# sensors.net
KiCad netlist of a schematic drawn in EAGLE
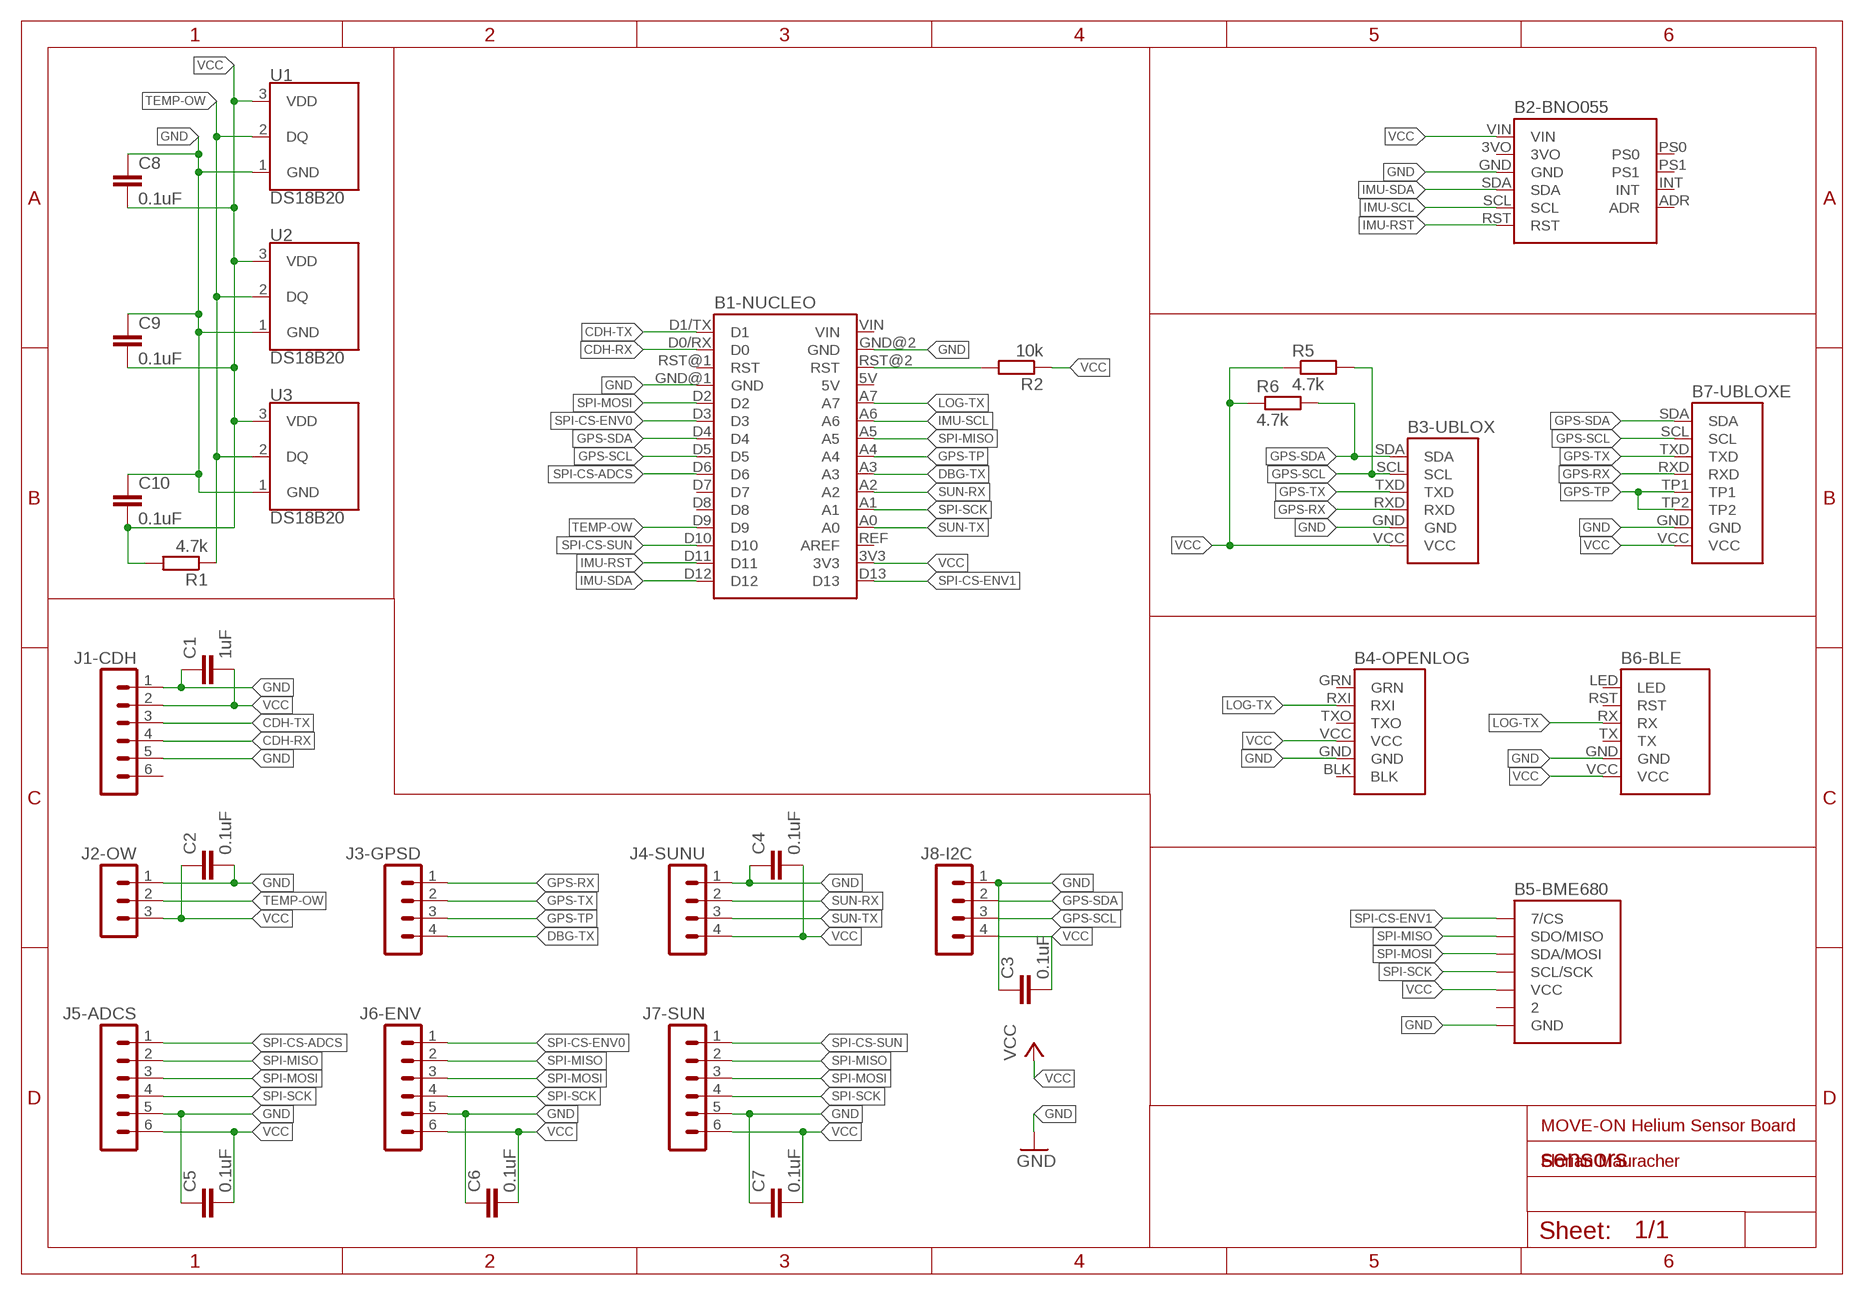
[diagram p0: schematic, sheet 1]

(export (version "E")
  (design (tool "Eeschema 10.0.6"))
  (components
    (comp (ref "B1-NUCLEO")
      (value "NUCLEO-32BO")
      (footprint "eagle-import:NUCLEO-32")
      (libsource (lib "eagle-import") (part "NUCLEO-32BO"))
    )
    (comp (ref "B2-BNO055")
      (value "BOSCH-BNO055BO")
      (footprint "eagle-import:BOSCH-BNO055")
      (libsource (lib "eagle-import") (part "BOSCH-BNO055BO"))
    )
    (comp (ref "B3-UBLOX")
      (value "UPUTRONICS-UBLOX-PICOBO")
      (footprint "eagle-import:UPUTRONICS-UBLOX-PICO")
      (libsource (lib "eagle-import") (part "UPUTRONICS-UBLOX-PICOBO"))
    )
    (comp (ref "B4-OPENLOG")
      (value "SPARKFUN-OPENLOGBO")
      (footprint "eagle-import:SPARKFUN-OPENLOG")
      (libsource (lib "eagle-import") (part "SPARKFUN-OPENLOGBO"))
    )
    (comp (ref "B5-BME680")
      (value "WATTEROT-BME680BO")
      (footprint "eagle-import:WATTEROT-BME680")
      (libsource (lib "eagle-import") (part "WATTEROT-BME680BO"))
    )
    (comp (ref "B6-BLE")
      (value "HUAMAO-HM-11BO")
      (footprint "eagle-import:HUAMAO-HM-11")
      (libsource (lib "eagle-import") (part "HUAMAO-HM-11BO"))
    )
    (comp (ref "B7-UBLOXE")
      (value "UPUTRONICS-UBLOX-M8Q")
      (footprint "eagle-import:UPUTRONICS-UBLOX-M8Q")
      (libsource (lib "eagle-import") (part "UPUTRONICS-UBLOX-M8Q"))
    )
    (comp (ref "C1")
      (value "1uF")
      (footprint "eagle-import:C2012")
      (libsource (lib "eagle-import") (part "C-EUC2012"))
    )
    (comp (ref "C2")
      (value "0.1uF")
      (footprint "eagle-import:C2012")
      (libsource (lib "eagle-import") (part "C-EUC2012"))
    )
    (comp (ref "C3")
      (value "0.1uF")
      (footprint "eagle-import:C2012")
      (libsource (lib "eagle-import") (part "C-EUC2012"))
    )
    (comp (ref "C4")
      (value "0.1uF")
      (footprint "eagle-import:C2012")
      (libsource (lib "eagle-import") (part "C-EUC2012"))
    )
    (comp (ref "C5")
      (value "0.1uF")
      (footprint "eagle-import:C2012")
      (libsource (lib "eagle-import") (part "C-EUC2012"))
    )
    (comp (ref "C6")
      (value "0.1uF")
      (footprint "eagle-import:C2012")
      (libsource (lib "eagle-import") (part "C-EUC2012"))
    )
    (comp (ref "C7")
      (value "0.1uF")
      (footprint "eagle-import:C2012")
      (libsource (lib "eagle-import") (part "C-EUC2012"))
    )
    (comp (ref "C8")
      (value "0.1uF")
      (footprint "eagle-import:C2012")
      (libsource (lib "eagle-import") (part "C-EUC2012"))
    )
    (comp (ref "C9")
      (value "0.1uF")
      (footprint "eagle-import:C2012")
      (libsource (lib "eagle-import") (part "C-EUC2012"))
    )
    (comp (ref "C10")
      (value "0.1uF")
      (footprint "eagle-import:C2012")
      (libsource (lib "eagle-import") (part "C-EUC2012"))
    )
    (comp (ref "J1-CDH")
      (value "90136-106")
      (footprint "eagle-import:90136-1_06")
      (libsource (lib "eagle-import") (part "90136-1?06"))
    )
    (comp (ref "J2-OW")
      (value "90136-103")
      (footprint "eagle-import:90136-1_03")
      (libsource (lib "eagle-import") (part "90136-1?03"))
    )
    (comp (ref "J3-GPSD")
      (value "90136-104")
      (footprint "eagle-import:90136-1_04")
      (libsource (lib "eagle-import") (part "90136-1?04"))
    )
    (comp (ref "J4-SUNU")
      (value "90136-104")
      (footprint "eagle-import:90136-1_04")
      (libsource (lib "eagle-import") (part "90136-1?04"))
    )
    (comp (ref "J5-ADCS")
      (value "90136-106")
      (footprint "eagle-import:90136-1_06")
      (libsource (lib "eagle-import") (part "90136-1?06"))
    )
    (comp (ref "J6-ENV")
      (value "90136-106")
      (footprint "eagle-import:90136-1_06")
      (libsource (lib "eagle-import") (part "90136-1?06"))
    )
    (comp (ref "J7-SUN")
      (value "90136-106")
      (footprint "eagle-import:90136-1_06")
      (libsource (lib "eagle-import") (part "90136-1?06"))
    )
    (comp (ref "J8-I2C")
      (value "90136-104")
      (footprint "eagle-import:90136-1_04")
      (libsource (lib "eagle-import") (part "90136-1?04"))
    )
    (comp (ref "R1")
      (value "4.7k")
      (footprint "eagle-import:R2012")
      (libsource (lib "eagle-import") (part "R-EU_R2012"))
    )
    (comp (ref "R2")
      (value "10k")
      (footprint "eagle-import:R2012")
      (libsource (lib "eagle-import") (part "R-EU_R2012"))
    )
    (comp (ref "R5")
      (value "4.7k")
      (footprint "eagle-import:R2012")
      (libsource (lib "eagle-import") (part "R-EU_R2012"))
    )
    (comp (ref "R6")
      (value "4.7k")
      (footprint "eagle-import:R2012")
      (libsource (lib "eagle-import") (part "R-EU_R2012"))
    )
    (comp (ref "U1")
      (value "DS18B20")
      (footprint "eagle-import:TO-92-AMMO")
      (libsource (lib "eagle-import") (part "DS18B20"))
    )
    (comp (ref "U2")
      (value "DS18B20")
      (footprint "eagle-import:TO-92-AMMO")
      (libsource (lib "eagle-import") (part "DS18B20"))
    )
    (comp (ref "U3")
      (value "DS18B20")
      (footprint "eagle-import:TO-92-AMMO")
      (libsource (lib "eagle-import") (part "DS18B20"))
    )
  )
  (nets
    (net (code "1") (name "/5V") (class "Default")
      (node (ref "B1-NUCLEO") (pin "5V") (pinfunction "5V_5V") (pintype "power_in"))
    )
    (net (code "2") (name "/GRN") (class "Default")
      (node (ref "B4-OPENLOG") (pin "GRN") (pinfunction "GRN_GRN") (pintype "power_in"))
    )
    (net (code "3") (name "/VIN") (class "Default")
      (node (ref "B1-NUCLEO") (pin "VIN") (pinfunction "VIN_VIN") (pintype "power_in"))
    )
    (net (code "4") (name "CDH-RX") (class "Default")
      (node (ref "B1-NUCLEO") (pin "D0/RX") (pinfunction "D0_D0/RX") (pintype "bidirectional"))
      (node (ref "J1-CDH") (pin "4") (pinfunction "4_4") (pintype "passive"))
    )
    (net (code "5") (name "CDH-TX") (class "Default")
      (node (ref "B1-NUCLEO") (pin "D1/TX") (pinfunction "D1_D1/TX") (pintype "bidirectional"))
      (node (ref "J1-CDH") (pin "3") (pinfunction "3_3") (pintype "passive"))
    )
    (net (code "6") (name "DBG-TX") (class "Default")
      (node (ref "B1-NUCLEO") (pin "A3") (pinfunction "A3_A3") (pintype "bidirectional"))
      (node (ref "J3-GPSD") (pin "4") (pinfunction "4_4") (pintype "passive"))
    )
    (net (code "7") (name "GND") (class "Default")
      (node (ref "B1-NUCLEO") (pin "GND@1") (pinfunction "GND_GND@1") (pintype "power_in"))
      (node (ref "B1-NUCLEO") (pin "GND@2") (pinfunction "GND_GND@2") (pintype "power_in"))
      (node (ref "B2-BNO055") (pin "GND") (pinfunction "GND_GND") (pintype "power_in"))
      (node (ref "B3-UBLOX") (pin "GND") (pinfunction "GND_GND") (pintype "power_in"))
      (node (ref "B4-OPENLOG") (pin "GND") (pinfunction "GND_GND") (pintype "power_in"))
      (node (ref "B5-BME680") (pin "GND") (pinfunction "GND_GND") (pintype "power_in"))
      (node (ref "B6-BLE") (pin "GND") (pinfunction "GND_GND") (pintype "power_in"))
      (node (ref "B7-UBLOXE") (pin "GND") (pinfunction "GND_GND") (pintype "power_in"))
      (node (ref "C1") (pin "1") (pinfunction "1_1") (pintype "passive"))
      (node (ref "C10") (pin "1") (pinfunction "1_1") (pintype "passive"))
      (node (ref "C2") (pin "2") (pinfunction "2_2") (pintype "passive"))
      (node (ref "C3") (pin "1") (pinfunction "1_1") (pintype "passive"))
      (node (ref "C4") (pin "1") (pinfunction "1_1") (pintype "passive"))
      (node (ref "C5") (pin "1") (pinfunction "1_1") (pintype "passive"))
      (node (ref "C6") (pin "1") (pinfunction "1_1") (pintype "passive"))
      (node (ref "C7") (pin "1") (pinfunction "1_1") (pintype "passive"))
      (node (ref "C8") (pin "1") (pinfunction "1_1") (pintype "passive"))
      (node (ref "C9") (pin "1") (pinfunction "1_1") (pintype "passive"))
      (node (ref "J1-CDH") (pin "1") (pinfunction "1_1") (pintype "passive"))
      (node (ref "J1-CDH") (pin "5") (pinfunction "5_5") (pintype "passive"))
      (node (ref "J2-OW") (pin "1") (pinfunction "1_1") (pintype "passive"))
      (node (ref "J4-SUNU") (pin "1") (pinfunction "1_1") (pintype "passive"))
      (node (ref "J5-ADCS") (pin "5") (pinfunction "5_5") (pintype "passive"))
      (node (ref "J6-ENV") (pin "5") (pinfunction "5_5") (pintype "passive"))
      (node (ref "J7-SUN") (pin "5") (pinfunction "5_5") (pintype "passive"))
      (node (ref "J8-I2C") (pin "1") (pinfunction "1_1") (pintype "passive"))
      (node (ref "U1") (pin "1") (pinfunction "GND_1") (pintype "power_in"))
      (node (ref "U2") (pin "1") (pinfunction "GND_1") (pintype "power_in"))
      (node (ref "U3") (pin "1") (pinfunction "GND_1") (pintype "power_in"))
    )
    (net (code "8") (name "GPS-RX") (class "Default")
      (node (ref "B3-UBLOX") (pin "RXD") (pinfunction "RXD_RXD") (pintype "bidirectional"))
      (node (ref "B7-UBLOXE") (pin "RXD") (pinfunction "RXD_RXD") (pintype "bidirectional"))
      (node (ref "J3-GPSD") (pin "1") (pinfunction "1_1") (pintype "passive"))
    )
    (net (code "9") (name "GPS-SCL") (class "Default")
      (node (ref "B1-NUCLEO") (pin "D5") (pinfunction "D5_D5") (pintype "bidirectional"))
      (node (ref "B3-UBLOX") (pin "SCL") (pinfunction "SCL_SCL") (pintype "bidirectional"))
      (node (ref "B7-UBLOXE") (pin "SCL") (pinfunction "SCL_SCL") (pintype "bidirectional"))
      (node (ref "J8-I2C") (pin "3") (pinfunction "3_3") (pintype "passive"))
      (node (ref "R5") (pin "2") (pinfunction "2_2") (pintype "passive"))
    )
    (net (code "10") (name "GPS-SDA") (class "Default")
      (node (ref "B1-NUCLEO") (pin "D4") (pinfunction "D4_D4") (pintype "bidirectional"))
      (node (ref "B3-UBLOX") (pin "SDA") (pinfunction "SDA_SDA") (pintype "bidirectional"))
      (node (ref "B7-UBLOXE") (pin "SDA") (pinfunction "SDA_SDA") (pintype "bidirectional"))
      (node (ref "J8-I2C") (pin "2") (pinfunction "2_2") (pintype "passive"))
      (node (ref "R6") (pin "2") (pinfunction "2_2") (pintype "passive"))
    )
    (net (code "11") (name "GPS-TP") (class "Default")
      (node (ref "B1-NUCLEO") (pin "A4") (pinfunction "A4_A4") (pintype "bidirectional"))
      (node (ref "B7-UBLOXE") (pin "TP1") (pinfunction "TP1_TP1") (pintype "bidirectional"))
      (node (ref "B7-UBLOXE") (pin "TP2") (pinfunction "TP2_TP2") (pintype "bidirectional"))
      (node (ref "J3-GPSD") (pin "3") (pinfunction "3_3") (pintype "passive"))
    )
    (net (code "12") (name "GPS-TX") (class "Default")
      (node (ref "B3-UBLOX") (pin "TXD") (pinfunction "TXD_TXD") (pintype "bidirectional"))
      (node (ref "B7-UBLOXE") (pin "TXD") (pinfunction "TXD_TXD") (pintype "bidirectional"))
      (node (ref "J3-GPSD") (pin "2") (pinfunction "2_2") (pintype "passive"))
    )
    (net (code "13") (name "IMU-RST") (class "Default")
      (node (ref "B1-NUCLEO") (pin "D11") (pinfunction "D11_D11") (pintype "bidirectional"))
      (node (ref "B2-BNO055") (pin "RST") (pinfunction "RST_RST") (pintype "bidirectional"))
    )
    (net (code "14") (name "IMU-SCL") (class "Default")
      (node (ref "B1-NUCLEO") (pin "A6") (pinfunction "A6_A6") (pintype "bidirectional"))
      (node (ref "B2-BNO055") (pin "SCL") (pinfunction "SCL_SCL") (pintype "bidirectional"))
    )
    (net (code "15") (name "IMU-SDA") (class "Default")
      (node (ref "B1-NUCLEO") (pin "D12") (pinfunction "D12_D12") (pintype "bidirectional"))
      (node (ref "B2-BNO055") (pin "SDA") (pinfunction "SDA_SDA") (pintype "bidirectional"))
    )
    (net (code "16") (name "LOG-TX") (class "Default")
      (node (ref "B1-NUCLEO") (pin "A7") (pinfunction "A7_A7") (pintype "bidirectional"))
      (node (ref "B4-OPENLOG") (pin "RXI") (pinfunction "RXI_RXI") (pintype "input"))
      (node (ref "B6-BLE") (pin "RX") (pinfunction "RX_RX") (pintype "input"))
    )
    (net (code "17") (name "Net-(B1-NUCLEO-RST-PadRST@2)") (class "Default")
      (node (ref "B1-NUCLEO") (pin "RST@2") (pinfunction "RST_RST@2") (pintype "bidirectional"))
      (node (ref "R2") (pin "2") (pinfunction "2_2") (pintype "passive"))
    )
    (net (code "18") (name "SPI-CS-ADCS") (class "Default")
      (node (ref "B1-NUCLEO") (pin "D6") (pinfunction "D6_D6") (pintype "bidirectional"))
      (node (ref "J5-ADCS") (pin "1") (pinfunction "1_1") (pintype "passive"))
    )
    (net (code "19") (name "SPI-CS-ENV0") (class "Default")
      (node (ref "B1-NUCLEO") (pin "D3") (pinfunction "D3_D3") (pintype "bidirectional"))
      (node (ref "J6-ENV") (pin "1") (pinfunction "1_1") (pintype "passive"))
    )
    (net (code "20") (name "SPI-CS-ENV1") (class "Default")
      (node (ref "B1-NUCLEO") (pin "D13") (pinfunction "D13_D13") (pintype "bidirectional"))
      (node (ref "B5-BME680") (pin "CS") (pinfunction "7/CS_CS") (pintype "input"))
    )
    (net (code "21") (name "SPI-CS-SUN") (class "Default")
      (node (ref "B1-NUCLEO") (pin "D10") (pinfunction "D10_D10") (pintype "bidirectional"))
      (node (ref "J7-SUN") (pin "1") (pinfunction "1_1") (pintype "passive"))
    )
    (net (code "22") (name "SPI-MISO") (class "Default")
      (node (ref "B1-NUCLEO") (pin "A5") (pinfunction "A5_A5") (pintype "bidirectional"))
      (node (ref "B5-BME680") (pin "SDO/MISO") (pinfunction "SDO/MISO_SDO/MISO") (pintype "output"))
      (node (ref "J5-ADCS") (pin "2") (pinfunction "2_2") (pintype "passive"))
      (node (ref "J6-ENV") (pin "2") (pinfunction "2_2") (pintype "passive"))
      (node (ref "J7-SUN") (pin "2") (pinfunction "2_2") (pintype "passive"))
    )
    (net (code "23") (name "SPI-MOSI") (class "Default")
      (node (ref "B1-NUCLEO") (pin "D2") (pinfunction "D2_D2") (pintype "bidirectional"))
      (node (ref "B5-BME680") (pin "SDA/MOSI") (pinfunction "SDA/MOSI_SDA/MOSI") (pintype "input"))
      (node (ref "J5-ADCS") (pin "3") (pinfunction "3_3") (pintype "passive"))
      (node (ref "J6-ENV") (pin "3") (pinfunction "3_3") (pintype "passive"))
      (node (ref "J7-SUN") (pin "3") (pinfunction "3_3") (pintype "passive"))
    )
    (net (code "24") (name "SPI-SCK") (class "Default")
      (node (ref "B1-NUCLEO") (pin "A1") (pinfunction "A1_A1") (pintype "bidirectional"))
      (node (ref "B5-BME680") (pin "SCL/SCK") (pinfunction "SCL/SCK_SCL/SCK") (pintype "input"))
      (node (ref "J5-ADCS") (pin "4") (pinfunction "4_4") (pintype "passive"))
      (node (ref "J6-ENV") (pin "4") (pinfunction "4_4") (pintype "passive"))
      (node (ref "J7-SUN") (pin "4") (pinfunction "4_4") (pintype "passive"))
    )
    (net (code "25") (name "SUN-RX") (class "Default")
      (node (ref "B1-NUCLEO") (pin "A2") (pinfunction "A2_A2") (pintype "bidirectional"))
      (node (ref "J4-SUNU") (pin "2") (pinfunction "2_2") (pintype "passive"))
    )
    (net (code "26") (name "SUN-TX") (class "Default")
      (node (ref "B1-NUCLEO") (pin "A0") (pinfunction "A0_A0") (pintype "bidirectional"))
      (node (ref "J4-SUNU") (pin "3") (pinfunction "3_3") (pintype "passive"))
    )
    (net (code "27") (name "TEMP-OW") (class "Default")
      (node (ref "B1-NUCLEO") (pin "D9") (pinfunction "D9_D9") (pintype "bidirectional"))
      (node (ref "J2-OW") (pin "2") (pinfunction "2_2") (pintype "passive"))
      (node (ref "R1") (pin "1") (pinfunction "1_1") (pintype "passive"))
      (node (ref "U1") (pin "2") (pinfunction "DQ_2") (pintype "bidirectional"))
      (node (ref "U2") (pin "2") (pinfunction "DQ_2") (pintype "bidirectional"))
      (node (ref "U3") (pin "2") (pinfunction "DQ_2") (pintype "bidirectional"))
    )
    (net (code "28") (name "VCC") (class "Default")
      (node (ref "B1-NUCLEO") (pin "3V3") (pinfunction "3V3_3V3") (pintype "power_in"))
      (node (ref "B2-BNO055") (pin "VIN") (pinfunction "VIN_VIN") (pintype "power_in"))
      (node (ref "B3-UBLOX") (pin "VCC") (pinfunction "VCC_VCC") (pintype "power_in"))
      (node (ref "B4-OPENLOG") (pin "VCC") (pinfunction "VCC_VCC") (pintype "power_in"))
      (node (ref "B5-BME680") (pin "VCC") (pinfunction "VCC_VCC") (pintype "power_in"))
      (node (ref "B6-BLE") (pin "VCC") (pinfunction "VCC_VCC") (pintype "power_in"))
      (node (ref "B7-UBLOXE") (pin "VCC") (pinfunction "VCC_VCC") (pintype "power_in"))
      (node (ref "C1") (pin "2") (pinfunction "2_2") (pintype "passive"))
      (node (ref "C10") (pin "2") (pinfunction "2_2") (pintype "passive"))
      (node (ref "C2") (pin "1") (pinfunction "1_1") (pintype "passive"))
      (node (ref "C3") (pin "2") (pinfunction "2_2") (pintype "passive"))
      (node (ref "C4") (pin "2") (pinfunction "2_2") (pintype "passive"))
      (node (ref "C5") (pin "2") (pinfunction "2_2") (pintype "passive"))
      (node (ref "C6") (pin "2") (pinfunction "2_2") (pintype "passive"))
      (node (ref "C7") (pin "2") (pinfunction "2_2") (pintype "passive"))
      (node (ref "C8") (pin "2") (pinfunction "2_2") (pintype "passive"))
      (node (ref "C9") (pin "2") (pinfunction "2_2") (pintype "passive"))
      (node (ref "J1-CDH") (pin "2") (pinfunction "2_2") (pintype "passive"))
      (node (ref "J2-OW") (pin "3") (pinfunction "3_3") (pintype "passive"))
      (node (ref "J4-SUNU") (pin "4") (pinfunction "4_4") (pintype "passive"))
      (node (ref "J5-ADCS") (pin "6") (pinfunction "6_6") (pintype "passive"))
      (node (ref "J6-ENV") (pin "6") (pinfunction "6_6") (pintype "passive"))
      (node (ref "J7-SUN") (pin "6") (pinfunction "6_6") (pintype "passive"))
      (node (ref "J8-I2C") (pin "4") (pinfunction "4_4") (pintype "passive"))
      (node (ref "R1") (pin "2") (pinfunction "2_2") (pintype "passive"))
      (node (ref "R2") (pin "1") (pinfunction "1_1") (pintype "passive"))
      (node (ref "R5") (pin "1") (pinfunction "1_1") (pintype "passive"))
      (node (ref "R6") (pin "1") (pinfunction "1_1") (pintype "passive"))
      (node (ref "U1") (pin "3") (pinfunction "VDD_3") (pintype "power_in"))
      (node (ref "U2") (pin "3") (pinfunction "VDD_3") (pintype "power_in"))
      (node (ref "U3") (pin "3") (pinfunction "VDD_3") (pintype "power_in"))
    )
    (net (code "29") (name "unconnected-(B1-NUCLEO-AREF-PadREF)") (class "Default")
      (node (ref "B1-NUCLEO") (pin "REF") (pinfunction "AREF_REF") (pintype "bidirectional"))
    )
    (net (code "30") (name "unconnected-(B1-NUCLEO-PadD7)") (class "Default")
      (node (ref "B1-NUCLEO") (pin "D7") (pinfunction "D7_D7") (pintype "bidirectional"))
    )
    (net (code "31") (name "unconnected-(B1-NUCLEO-PadD8)") (class "Default")
      (node (ref "B1-NUCLEO") (pin "D8") (pinfunction "D8_D8") (pintype "bidirectional"))
    )
    (net (code "32") (name "unconnected-(B1-NUCLEO-RST-PadRST@1)") (class "Default")
      (node (ref "B1-NUCLEO") (pin "RST@1") (pinfunction "RST_RST@1") (pintype "bidirectional"))
    )
    (net (code "33") (name "unconnected-(B2-BNO055-Pad3VO)") (class "Default")
      (node (ref "B2-BNO055") (pin "3VO") (pinfunction "3VO_3VO") (pintype "bidirectional"))
    )
    (net (code "34") (name "unconnected-(B2-BNO055-PadADR)") (class "Default")
      (node (ref "B2-BNO055") (pin "ADR") (pinfunction "ADR_ADR") (pintype "bidirectional"))
    )
    (net (code "35") (name "unconnected-(B2-BNO055-PadINT)") (class "Default")
      (node (ref "B2-BNO055") (pin "INT") (pinfunction "INT_INT") (pintype "bidirectional"))
    )
    (net (code "36") (name "unconnected-(B2-BNO055-PadPS0)") (class "Default")
      (node (ref "B2-BNO055") (pin "PS0") (pinfunction "PS0_PS0") (pintype "bidirectional"))
    )
    (net (code "37") (name "unconnected-(B2-BNO055-PadPS1)") (class "Default")
      (node (ref "B2-BNO055") (pin "PS1") (pinfunction "PS1_PS1") (pintype "bidirectional"))
    )
    (net (code "38") (name "unconnected-(B4-OPENLOG-PadBLK)") (class "Default")
      (node (ref "B4-OPENLOG") (pin "BLK") (pinfunction "BLK_BLK") (pintype "bidirectional"))
    )
    (net (code "39") (name "unconnected-(B4-OPENLOG-PadTXO)") (class "Default")
      (node (ref "B4-OPENLOG") (pin "TXO") (pinfunction "TXO_TXO") (pintype "output"))
    )
    (net (code "40") (name "unconnected-(B5-BME680-Pad2)") (class "Default")
      (node (ref "B5-BME680") (pin "2") (pinfunction "2_2") (pintype "no_connect"))
    )
    (net (code "41") (name "unconnected-(B6-BLE-PadLED)") (class "Default")
      (node (ref "B6-BLE") (pin "LED") (pinfunction "LED_LED") (pintype "bidirectional"))
    )
    (net (code "42") (name "unconnected-(B6-BLE-PadRST)") (class "Default")
      (node (ref "B6-BLE") (pin "RST") (pinfunction "RST_RST") (pintype "bidirectional"))
    )
    (net (code "43") (name "unconnected-(B6-BLE-PadTX)") (class "Default")
      (node (ref "B6-BLE") (pin "TX") (pinfunction "TX_TX") (pintype "output"))
    )
    (net (code "44") (name "unconnected-(J1-CDH-Pad6)") (class "Default")
      (node (ref "J1-CDH") (pin "6") (pinfunction "6_6") (pintype "passive"))
    )
  )
)
